# microcontroller.net
KiCad netlist of a schematic drawn in Altium Designer
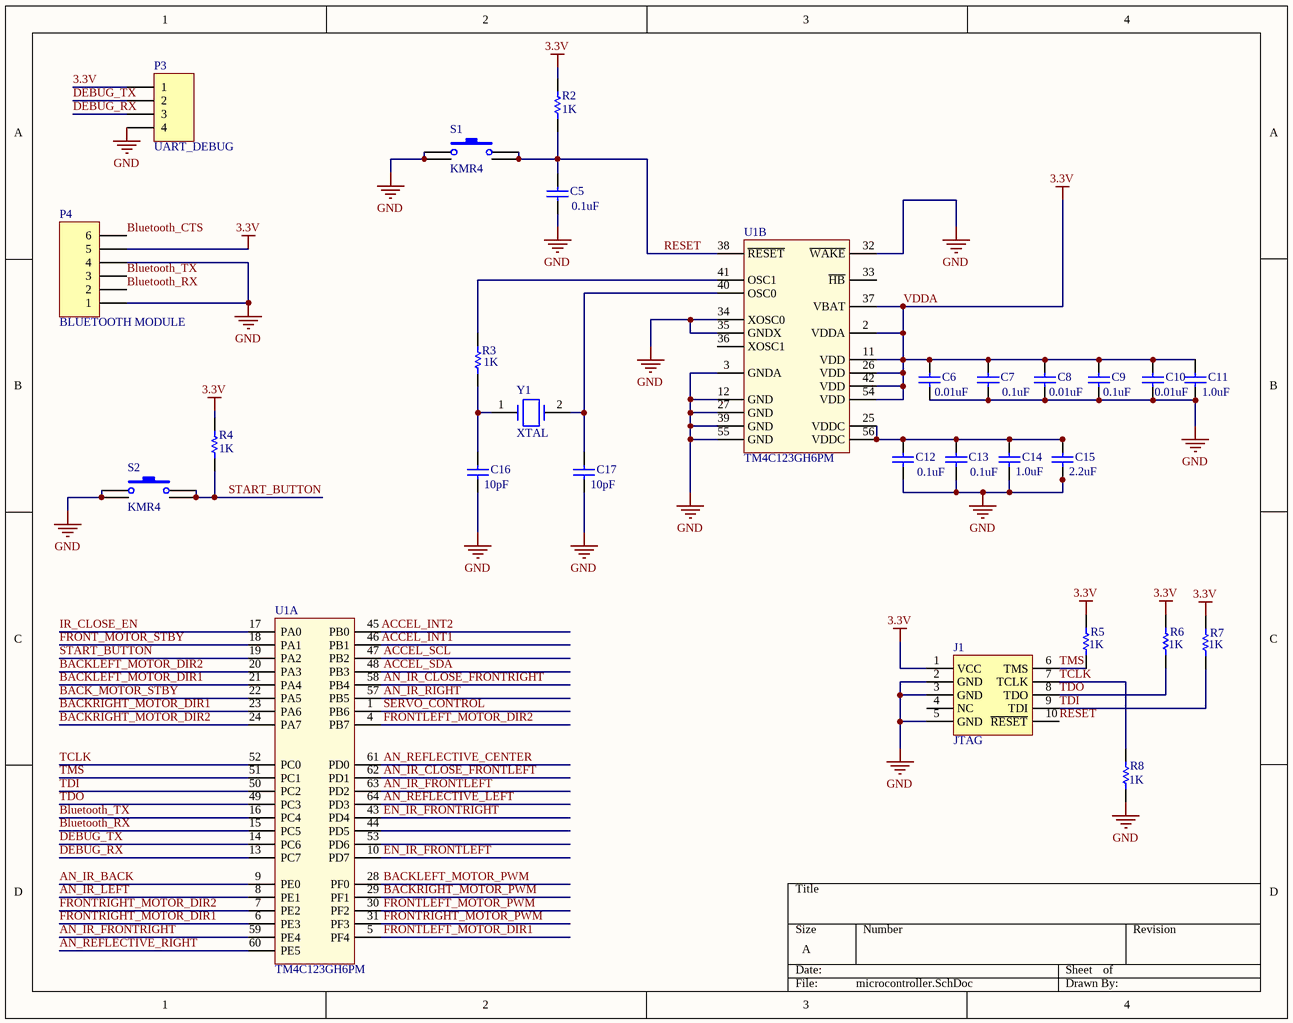
[diagram p0: microcontroller.SchDoc]

(export (version "E")
  (design (tool "Eeschema 10.0.6"))
  (components
    (comp (ref "C5")
      (value "0.1uF")
      (footprint "0805")
      (description "Capacitor")
      (fields (field (name "Comment") "Cap"))
      (libsource (lib "passives") (part "Cap"))
    )
    (comp (ref "C6")
      (value "0.01uF")
      (footprint "0805")
      (description "Capacitor")
      (fields (field (name "Comment") "Cap"))
      (libsource (lib "passives") (part "Cap"))
    )
    (comp (ref "C7")
      (value "0.1uF")
      (footprint "0805")
      (description "Capacitor")
      (fields (field (name "Comment") "Cap"))
      (libsource (lib "passives") (part "Cap"))
    )
    (comp (ref "C8")
      (value "0.01uF")
      (footprint "0805")
      (description "Capacitor")
      (fields (field (name "Comment") "Cap"))
      (libsource (lib "passives") (part "Cap"))
    )
    (comp (ref "C9")
      (value "0.1uF")
      (footprint "0805")
      (description "Capacitor")
      (fields (field (name "Comment") "Cap"))
      (libsource (lib "passives") (part "Cap"))
    )
    (comp (ref "C10")
      (value "0.01uF")
      (footprint "0805")
      (description "Capacitor")
      (fields (field (name "Comment") "Cap"))
      (libsource (lib "passives") (part "Cap"))
    )
    (comp (ref "C11")
      (value "1.0uF")
      (footprint "0805")
      (description "Capacitor")
      (fields (field (name "Comment") "Cap"))
      (libsource (lib "passives") (part "Cap"))
    )
    (comp (ref "C12")
      (value "0.1uF")
      (footprint "0805")
      (description "Capacitor")
      (fields (field (name "Comment") "Cap"))
      (libsource (lib "passives") (part "Cap"))
    )
    (comp (ref "C13")
      (value "0.1uF")
      (footprint "0805")
      (description "Capacitor")
      (fields (field (name "Comment") "Cap"))
      (libsource (lib "passives") (part "Cap"))
    )
    (comp (ref "C14")
      (value "1.0uF")
      (footprint "0805")
      (description "Capacitor")
      (fields (field (name "Comment") "Cap"))
      (libsource (lib "passives") (part "Cap"))
    )
    (comp (ref "C15")
      (value "2.2uF")
      (footprint "0805")
      (description "Capacitor")
      (fields (field (name "Comment") "Cap"))
      (libsource (lib "passives") (part "Cap"))
    )
    (comp (ref "C16")
      (value "10pF")
      (footprint "0805")
      (description "Capacitor")
      (fields (field (name "Comment") "Cap"))
      (libsource (lib "passives") (part "Cap"))
    )
    (comp (ref "C17")
      (value "10pF")
      (footprint "0805")
      (description "Capacitor")
      (fields (field (name "Comment") "Cap"))
      (libsource (lib "passives") (part "Cap"))
    )
    (comp (ref "J1")
      (value "JTAG")
      (footprint "TAG Connect 10p")
      (description "10-Pin JTAG Connector for Cortex M4 etc.")
      (libsource (lib "connectors") (part "10-Pin JTAG ARM"))
    )
    (comp (ref "P3")
      (value "UART_DEBUG")
      (footprint "HDR1X4")
      (description "Header, 4-Pin")
      (fields (field (name "PUBLISHER") "Altium Limited"))
      (libsource (lib "Miscellaneous Connectors") (part "Header 4"))
    )
    (comp (ref "P4")
      (value "BLUETOOTH MODULE")
      (footprint "HDR1X6")
      (description "Header, 6-Pin")
      (fields (field (name "PUBLISHER") "Altium Limited"))
      (libsource (lib "Miscellaneous Connectors") (part "Header 6"))
    )
    (comp (ref "R2")
      (value "1K")
      (footprint "0805")
      (description "Resistor")
      (fields (field (name "PUBLISHER") "Altium Limited"))
      (libsource (lib "passives") (part "Resistor"))
    )
    (comp (ref "R3")
      (value "1K")
      (footprint "0805")
      (description "Resistor")
      (fields (field (name "PUBLISHER") "Altium Limited"))
      (libsource (lib "passives") (part "Resistor"))
    )
    (comp (ref "R4")
      (value "1K")
      (footprint "0805")
      (description "Resistor")
      (fields (field (name "PUBLISHER") "Altium Limited"))
      (libsource (lib "passives") (part "Resistor"))
    )
    (comp (ref "R5")
      (value "1K")
      (footprint "0805")
      (description "Resistor")
      (fields (field (name "PUBLISHER") "Altium Limited"))
      (libsource (lib "passives") (part "Resistor"))
    )
    (comp (ref "R6")
      (value "1K")
      (footprint "0805")
      (description "Resistor")
      (fields (field (name "PUBLISHER") "Altium Limited"))
      (libsource (lib "passives") (part "Resistor"))
    )
    (comp (ref "R7")
      (value "1K")
      (footprint "0805")
      (description "Resistor")
      (fields (field (name "PUBLISHER") "Altium Limited"))
      (libsource (lib "passives") (part "Resistor"))
    )
    (comp (ref "R8")
      (value "1K")
      (footprint "0805")
      (description "Resistor")
      (fields (field (name "PUBLISHER") "Altium Limited"))
      (libsource (lib "passives") (part "Resistor"))
    )
    (comp (ref "S1")
      (value "KMR4")
      (footprint "KMR4")
      (description "Switch")
      (fields (field (name "PUBLISHER") "Altium Limited"))
      (libsource (lib "switches") (part "SPST Tactile Switch"))
    )
    (comp (ref "S2")
      (value "KMR4")
      (footprint "KMR4")
      (description "Switch")
      (fields (field (name "PUBLISHER") "Altium Limited"))
      (libsource (lib "switches") (part "SPST Tactile Switch"))
    )
    (comp (ref "U1")
      (value "TM4C123GH6PM")
      (footprint "TSQFP50P1200X1200X145-64N")
      (description "Tiva C TM4C123GH6PM")
      (libsource (lib "microcontrollers") (part "TM4C123GH6PM"))
    )
    (comp (ref "Y1")
      (value "XTAL")
      (footprint "ABM3_SERIES")
      (description "Crystal Oscillator")
      (fields (field (name "PUBLISHER") "Altium Limited"))
      (libsource (lib "Devices") (part "XTAL"))
    )
  )
  (nets
    (net (code "1") (name "/ACCEL_INT1") (class "Default")
      (node (ref "U1") (pin "46") (pinfunction "PB1_46") (pintype "passive"))
    )
    (net (code "2") (name "/ACCEL_INT2") (class "Default")
      (node (ref "U1") (pin "45") (pinfunction "PB0_45") (pintype "passive"))
    )
    (net (code "3") (name "/ACCEL_SCL") (class "Default")
      (node (ref "U1") (pin "47") (pinfunction "PB2_47") (pintype "passive"))
    )
    (net (code "4") (name "/ACCEL_SDA") (class "Default")
      (node (ref "U1") (pin "48") (pinfunction "PB3_48") (pintype "passive"))
    )
    (net (code "5") (name "/AN_IR_BACK") (class "Default")
      (node (ref "U1") (pin "9") (pinfunction "PE0_9") (pintype "passive"))
    )
    (net (code "6") (name "/AN_IR_CLOSE_FRONTLEFT") (class "Default")
      (node (ref "U1") (pin "62") (pinfunction "PD1_62") (pintype "passive"))
    )
    (net (code "7") (name "/AN_IR_CLOSE_FRONTRIGHT") (class "Default")
      (node (ref "U1") (pin "58") (pinfunction "PB4_58") (pintype "passive"))
    )
    (net (code "8") (name "/AN_IR_FRONTLEFT") (class "Default")
      (node (ref "U1") (pin "63") (pinfunction "PD2_63") (pintype "passive"))
    )
    (net (code "9") (name "/AN_IR_FRONTRIGHT") (class "Default")
      (node (ref "U1") (pin "59") (pinfunction "PE4_59") (pintype "passive"))
    )
    (net (code "10") (name "/AN_IR_LEFT") (class "Default")
      (node (ref "U1") (pin "8") (pinfunction "PE1_8") (pintype "passive"))
    )
    (net (code "11") (name "/AN_IR_RIGHT") (class "Default")
      (node (ref "U1") (pin "57") (pinfunction "PB5_57") (pintype "passive"))
    )
    (net (code "12") (name "/AN_REFLECTIVE_CENTER") (class "Default")
      (node (ref "U1") (pin "61") (pinfunction "PD0_61") (pintype "passive"))
    )
    (net (code "13") (name "/AN_REFLECTIVE_LEFT") (class "Default")
      (node (ref "U1") (pin "64") (pinfunction "PD3_64") (pintype "passive"))
    )
    (net (code "14") (name "/AN_REFLECTIVE_RIGHT") (class "Default")
      (node (ref "U1") (pin "60") (pinfunction "PE5_60") (pintype "passive"))
    )
    (net (code "15") (name "/BACKLEFT_MOTOR_DIR1") (class "Default")
      (node (ref "U1") (pin "21") (pinfunction "PA4_21") (pintype "passive"))
    )
    (net (code "16") (name "/BACKLEFT_MOTOR_DIR2") (class "Default")
      (node (ref "U1") (pin "20") (pinfunction "PA3_20") (pintype "passive"))
    )
    (net (code "17") (name "/BACKLEFT_MOTOR_PWM") (class "Default")
      (node (ref "U1") (pin "28") (pinfunction "PF0_28") (pintype "passive"))
    )
    (net (code "18") (name "/BACKRIGHT_MOTOR_DIR1") (class "Default")
      (node (ref "U1") (pin "23") (pinfunction "PA6_23") (pintype "passive"))
    )
    (net (code "19") (name "/BACKRIGHT_MOTOR_DIR2") (class "Default")
      (node (ref "U1") (pin "24") (pinfunction "PA7_24") (pintype "passive"))
    )
    (net (code "20") (name "/BACKRIGHT_MOTOR_PWM") (class "Default")
      (node (ref "U1") (pin "29") (pinfunction "PF1_29") (pintype "passive"))
    )
    (net (code "21") (name "/BACK_MOTOR_STBY") (class "Default")
      (node (ref "U1") (pin "22") (pinfunction "PA5_22") (pintype "passive"))
    )
    (net (code "22") (name "/Bluetooth_CTS") (class "Default")
      (node (ref "P4") (pin "6") (pinfunction "6_6") (pintype "passive"))
    )
    (net (code "23") (name "/Bluetooth_RX") (class "Default")
      (node (ref "P4") (pin "2") (pinfunction "2_2") (pintype "passive"))
      (node (ref "U1") (pin "15") (pinfunction "PC5_15") (pintype "passive"))
    )
    (net (code "24") (name "/Bluetooth_TX") (class "Default")
      (node (ref "P4") (pin "3") (pinfunction "3_3") (pintype "passive"))
      (node (ref "U1") (pin "16") (pinfunction "PC4_16") (pintype "passive"))
    )
    (net (code "25") (name "/DEBUG_RX") (class "Default")
      (node (ref "P3") (pin "3") (pinfunction "3_3") (pintype "passive"))
      (node (ref "U1") (pin "13") (pinfunction "PC7_13") (pintype "passive"))
    )
    (net (code "26") (name "/DEBUG_TX") (class "Default")
      (node (ref "P3") (pin "2") (pinfunction "2_2") (pintype "passive"))
      (node (ref "U1") (pin "14") (pinfunction "PC6_14") (pintype "passive"))
    )
    (net (code "27") (name "/EN_IR_FRONTLEFT") (class "Default")
      (node (ref "U1") (pin "10") (pinfunction "PD7_10") (pintype "passive"))
    )
    (net (code "28") (name "/EN_IR_FRONTRIGHT") (class "Default")
      (node (ref "U1") (pin "43") (pinfunction "PD4_43") (pintype "passive"))
    )
    (net (code "29") (name "/FRONTLEFT_MOTOR_DIR1") (class "Default")
      (node (ref "U1") (pin "5") (pinfunction "PF4_5") (pintype "passive"))
    )
    (net (code "30") (name "/FRONTLEFT_MOTOR_DIR2") (class "Default")
      (node (ref "U1") (pin "4") (pinfunction "PB7_4") (pintype "passive"))
    )
    (net (code "31") (name "/FRONTLEFT_MOTOR_PWM") (class "Default")
      (node (ref "U1") (pin "30") (pinfunction "PF2_30") (pintype "passive"))
    )
    (net (code "32") (name "/FRONTRIGHT_MOTOR_DIR1") (class "Default")
      (node (ref "U1") (pin "6") (pinfunction "PE3_6") (pintype "passive"))
    )
    (net (code "33") (name "/FRONTRIGHT_MOTOR_DIR2") (class "Default")
      (node (ref "U1") (pin "7") (pinfunction "PE2_7") (pintype "passive"))
    )
    (net (code "34") (name "/FRONTRIGHT_MOTOR_PWM") (class "Default")
      (node (ref "U1") (pin "31") (pinfunction "PF3_31") (pintype "passive"))
    )
    (net (code "35") (name "/FRONT_MOTOR_STBY") (class "Default")
      (node (ref "U1") (pin "18") (pinfunction "PA1_18") (pintype "passive"))
    )
    (net (code "36") (name "/IR_CLOSE_EN") (class "Default")
      (node (ref "U1") (pin "17") (pinfunction "PA0_17") (pintype "passive"))
    )
    (net (code "37") (name "/RESET") (class "Default")
      (node (ref "C5") (pin "2") (pinfunction "2_2") (pintype "passive"))
      (node (ref "J1") (pin "10") (pinfunction "~{RESET}_10") (pintype "passive"))
      (node (ref "R2") (pin "1") (pinfunction "1_1") (pintype "passive"))
      (node (ref "S1") (pin "2") (pinfunction "2_2") (pintype "passive"))
      (node (ref "S1") (pin "4") (pinfunction "4_4") (pintype "passive"))
      (node (ref "U1") (pin "38") (pinfunction "~{RESET}_38") (pintype "passive"))
    )
    (net (code "38") (name "/SERVO_CONTROL") (class "Default")
      (node (ref "U1") (pin "1") (pinfunction "PB6_1") (pintype "passive"))
    )
    (net (code "39") (name "/START_BUTTON") (class "Default")
      (node (ref "R4") (pin "1") (pinfunction "1_1") (pintype "passive"))
      (node (ref "S2") (pin "2") (pinfunction "2_2") (pintype "passive"))
      (node (ref "S2") (pin "4") (pinfunction "4_4") (pintype "passive"))
      (node (ref "U1") (pin "19") (pinfunction "PA2_19") (pintype "passive"))
    )
    (net (code "40") (name "/TCLK") (class "Default")
      (node (ref "J1") (pin "7") (pinfunction "TCLK_7") (pintype "passive"))
      (node (ref "R8") (pin "2") (pinfunction "2_2") (pintype "passive"))
      (node (ref "U1") (pin "52") (pinfunction "PC0_52") (pintype "passive"))
    )
    (net (code "41") (name "/TDI") (class "Default")
      (node (ref "J1") (pin "9") (pinfunction "TDI_9") (pintype "passive"))
      (node (ref "R7") (pin "1") (pinfunction "1_1") (pintype "passive"))
      (node (ref "U1") (pin "50") (pinfunction "PC2_50") (pintype "passive"))
    )
    (net (code "42") (name "/TDO") (class "Default")
      (node (ref "J1") (pin "8") (pinfunction "TDO_8") (pintype "passive"))
      (node (ref "R6") (pin "1") (pinfunction "1_1") (pintype "passive"))
      (node (ref "U1") (pin "49") (pinfunction "PC3_49") (pintype "passive"))
    )
    (net (code "43") (name "/TMS") (class "Default")
      (node (ref "J1") (pin "6") (pinfunction "TMS_6") (pintype "passive"))
      (node (ref "R5") (pin "1") (pinfunction "1_1") (pintype "passive"))
      (node (ref "U1") (pin "51") (pinfunction "PC1_51") (pintype "passive"))
    )
    (net (code "44") (name "3.3V") (class "Default")
      (node (ref "C10") (pin "2") (pinfunction "2_2") (pintype "passive"))
      (node (ref "C11") (pin "2") (pinfunction "2_2") (pintype "passive"))
      (node (ref "C6") (pin "2") (pinfunction "2_2") (pintype "passive"))
      (node (ref "C7") (pin "2") (pinfunction "2_2") (pintype "passive"))
      (node (ref "C8") (pin "2") (pinfunction "2_2") (pintype "passive"))
      (node (ref "C9") (pin "2") (pinfunction "2_2") (pintype "passive"))
      (node (ref "J1") (pin "1") (pinfunction "VCC_1") (pintype "passive"))
      (node (ref "P3") (pin "1") (pinfunction "1_1") (pintype "passive"))
      (node (ref "P4") (pin "5") (pinfunction "5_5") (pintype "passive"))
      (node (ref "R2") (pin "2") (pinfunction "2_2") (pintype "passive"))
      (node (ref "R4") (pin "2") (pinfunction "2_2") (pintype "passive"))
      (node (ref "R5") (pin "2") (pinfunction "2_2") (pintype "passive"))
      (node (ref "R6") (pin "2") (pinfunction "2_2") (pintype "passive"))
      (node (ref "R7") (pin "2") (pinfunction "2_2") (pintype "passive"))
      (node (ref "U1") (pin "11") (pinfunction "VDD_11") (pintype "passive"))
      (node (ref "U1") (pin "2") (pinfunction "VDDA_2") (pintype "passive"))
      (node (ref "U1") (pin "26") (pinfunction "VDD_26") (pintype "passive"))
      (node (ref "U1") (pin "37") (pinfunction "VBAT_37") (pintype "passive"))
      (node (ref "U1") (pin "42") (pinfunction "VDD_42") (pintype "passive"))
      (node (ref "U1") (pin "54") (pinfunction "VDD_54") (pintype "passive"))
    )
    (net (code "45") (name "GND") (class "Default")
      (node (ref "C10") (pin "1") (pinfunction "1_1") (pintype "passive"))
      (node (ref "C11") (pin "1") (pinfunction "1_1") (pintype "passive"))
      (node (ref "C12") (pin "1") (pinfunction "1_1") (pintype "passive"))
      (node (ref "C13") (pin "1") (pinfunction "1_1") (pintype "passive"))
      (node (ref "C14") (pin "1") (pinfunction "1_1") (pintype "passive"))
      (node (ref "C15") (pin "1") (pinfunction "1_1") (pintype "passive"))
      (node (ref "C16") (pin "1") (pinfunction "1_1") (pintype "passive"))
      (node (ref "C17") (pin "1") (pinfunction "1_1") (pintype "passive"))
      (node (ref "C5") (pin "1") (pinfunction "1_1") (pintype "passive"))
      (node (ref "C6") (pin "1") (pinfunction "1_1") (pintype "passive"))
      (node (ref "C7") (pin "1") (pinfunction "1_1") (pintype "passive"))
      (node (ref "C8") (pin "1") (pinfunction "1_1") (pintype "passive"))
      (node (ref "C9") (pin "1") (pinfunction "1_1") (pintype "passive"))
      (node (ref "J1") (pin "2") (pinfunction "GND_2") (pintype "passive"))
      (node (ref "J1") (pin "3") (pinfunction "GND_3") (pintype "passive"))
      (node (ref "J1") (pin "5") (pinfunction "GND_5") (pintype "passive"))
      (node (ref "P3") (pin "4") (pinfunction "4_4") (pintype "passive"))
      (node (ref "P4") (pin "1") (pinfunction "1_1") (pintype "passive"))
      (node (ref "P4") (pin "4") (pinfunction "4_4") (pintype "passive"))
      (node (ref "R8") (pin "1") (pinfunction "1_1") (pintype "passive"))
      (node (ref "S1") (pin "1") (pinfunction "1_1") (pintype "passive"))
      (node (ref "S1") (pin "3") (pinfunction "3_3") (pintype "passive"))
      (node (ref "S2") (pin "1") (pinfunction "1_1") (pintype "passive"))
      (node (ref "S2") (pin "3") (pinfunction "3_3") (pintype "passive"))
      (node (ref "U1") (pin "12") (pinfunction "GND_12") (pintype "passive"))
      (node (ref "U1") (pin "27") (pinfunction "GND_27") (pintype "passive"))
      (node (ref "U1") (pin "3") (pinfunction "GNDA_3") (pintype "passive"))
      (node (ref "U1") (pin "32") (pinfunction "~{WAKE}_32") (pintype "passive"))
      (node (ref "U1") (pin "34") (pinfunction "XOSC0_34") (pintype "passive"))
      (node (ref "U1") (pin "35") (pinfunction "GNDX_35") (pintype "passive"))
      (node (ref "U1") (pin "39") (pinfunction "GND_39") (pintype "passive"))
      (node (ref "U1") (pin "55") (pinfunction "GND_55") (pintype "passive"))
    )
    (net (code "46") (name "Net-(C12-Pad2)") (class "Default")
      (node (ref "C12") (pin "2") (pinfunction "2_2") (pintype "passive"))
      (node (ref "C13") (pin "2") (pinfunction "2_2") (pintype "passive"))
      (node (ref "C14") (pin "2") (pinfunction "2_2") (pintype "passive"))
      (node (ref "C15") (pin "2") (pinfunction "2_2") (pintype "passive"))
      (node (ref "U1") (pin "25") (pinfunction "VDDC_25") (pintype "passive"))
      (node (ref "U1") (pin "56") (pinfunction "VDDC_56") (pintype "passive"))
    )
    (net (code "47") (name "Net-(U1B-OSC0)") (class "Default")
      (node (ref "C17") (pin "2") (pinfunction "2_2") (pintype "passive"))
      (node (ref "U1") (pin "40") (pinfunction "OSC0_40") (pintype "passive"))
      (node (ref "Y1") (pin "2") (pinfunction "OSC2_2") (pintype "passive"))
    )
    (net (code "48") (name "Net-(U1B-OSC1)") (class "Default")
      (node (ref "R3") (pin "2") (pinfunction "2_2") (pintype "passive"))
      (node (ref "U1") (pin "41") (pinfunction "OSC1_41") (pintype "passive"))
    )
    (net (code "49") (name "Net-(Y1-OSC1)") (class "Default")
      (node (ref "C16") (pin "2") (pinfunction "2_2") (pintype "passive"))
      (node (ref "R3") (pin "1") (pinfunction "1_1") (pintype "passive"))
      (node (ref "Y1") (pin "1") (pinfunction "OSC1_1") (pintype "passive"))
    )
    (net (code "50") (name "unconnected-(J1-NC-Pad4)") (class "Default")
      (node (ref "J1") (pin "4") (pinfunction "NC_4") (pintype "passive"))
    )
    (net (code "51") (name "unconnected-(U1A-PD5-Pad44)") (class "Default")
      (node (ref "U1") (pin "44") (pinfunction "PD5_44") (pintype "passive"))
    )
    (net (code "52") (name "unconnected-(U1A-PD6-Pad53)") (class "Default")
      (node (ref "U1") (pin "53") (pinfunction "PD6_53") (pintype "passive"))
    )
    (net (code "53") (name "unconnected-(U1B-XOSC1-Pad36)") (class "Default")
      (node (ref "U1") (pin "36") (pinfunction "XOSC1_36") (pintype "passive"))
    )
    (net (code "54") (name "unconnected-(U1B-~{HB}-Pad33)") (class "Default")
      (node (ref "U1") (pin "33") (pinfunction "~{HB}_33") (pintype "passive"))
    )
  )
)
